# mcp2221-breakout.net
KiCad netlist of a schematic drawn in EAGLE
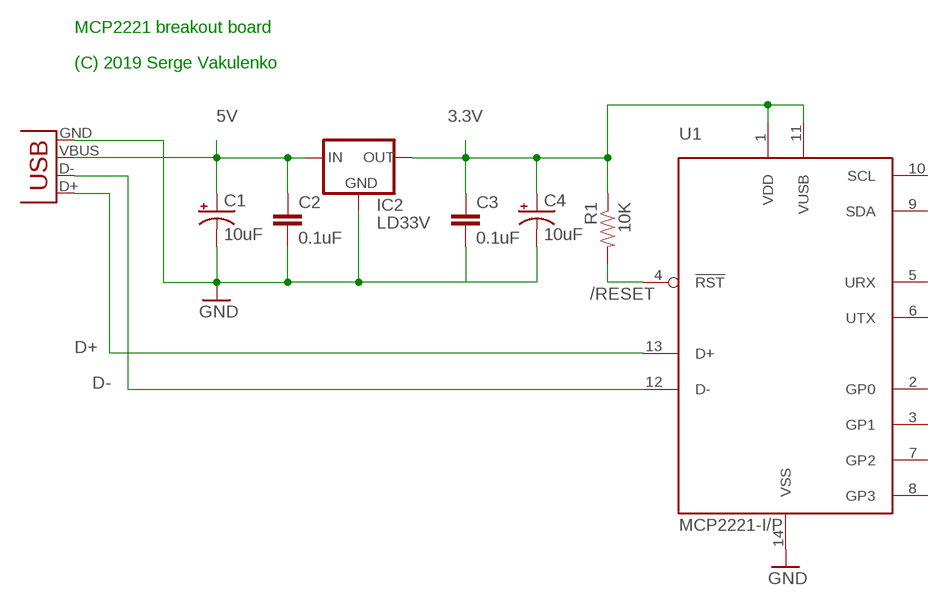
[diagram p0: schematic, sheet 1]

(export (version "E")
  (design (tool "Eeschema 10.0.6"))
  (components
    (comp (ref "C1")
      (value "10uF")
      (footprint "eagle-import:CPOL-RADIAL-10UF-25V")
      (libsource (lib "eagle-import") (part "CAP_POLPTH2"))
    )
    (comp (ref "C2")
      (value "0.1uF")
      (footprint "eagle-import:CAP-PTH-SMALL")
      (libsource (lib "eagle-import") (part "CAPPTH"))
    )
    (comp (ref "C3")
      (value "0.1uF")
      (footprint "eagle-import:CAP-PTH-5MM")
      (libsource (lib "eagle-import") (part "CAPPTH1"))
    )
    (comp (ref "C4")
      (value "10uF")
      (footprint "eagle-import:CPOL-RADIAL-10UF-25V")
      (libsource (lib "eagle-import") (part "CAP_POLPTH2"))
    )
    (comp (ref "IC2")
      (value "LD33V")
      (footprint "eagle-import:78XXL")
      (libsource (lib "eagle-import") (part "V_REG_78XXSIDE"))
    )
    (comp (ref "R1")
      (value "10K")
      (footprint "eagle-import:AXIAL-0.3")
      (libsource (lib "eagle-import") (part "RESISTORPTH1"))
    )
    (comp (ref "U1")
      (value "MCP2221-I/P")
      (footprint "eagle-import:DIL14")
      (libsource (lib "eagle-import") (part "MCP2221-I/P"))
    )
    (comp (ref "X1")
      (value "USBPTH")
      (footprint "eagle-import:USB-B-PTH")
      (libsource (lib "eagle-import") (part "USBPTH"))
    )
  )
  (nets
    (net (code "1") (name "/3.3V") (class "Default")
      (node (ref "C3") (pin "1") (pinfunction "1_1") (pintype "passive"))
      (node (ref "C4") (pin "1") (pinfunction "+_1") (pintype "passive"))
      (node (ref "IC2") (pin "OUT") (pinfunction "OUT_OUT") (pintype "output"))
      (node (ref "R1") (pin "P$1") (pinfunction "1_P$1") (pintype "passive"))
      (node (ref "U1") (pin "1") (pinfunction "VDD_1") (pintype "power_in"))
      (node (ref "U1") (pin "11") (pinfunction "VUSB_11") (pintype "power_in"))
    )
    (net (code "2") (name "/5V") (class "Default")
      (node (ref "C1") (pin "1") (pinfunction "+_1") (pintype "passive"))
      (node (ref "C2") (pin "1") (pinfunction "1_1") (pintype "passive"))
      (node (ref "IC2") (pin "IN") (pinfunction "IN_IN") (pintype "input"))
      (node (ref "X1") (pin "VBUS") (pinfunction "VBUS_VBUS") (pintype "bidirectional"))
    )
    (net (code "3") (name "/D+") (class "Default")
      (node (ref "U1") (pin "13") (pinfunction "D+_13") (pintype "bidirectional"))
      (node (ref "X1") (pin "D+") (pinfunction "D+_D+") (pintype "bidirectional"))
    )
    (net (code "4") (name "/D-") (class "Default")
      (node (ref "U1") (pin "12") (pinfunction "D-_12") (pintype "bidirectional"))
      (node (ref "X1") (pin "D-") (pinfunction "D-_D-") (pintype "bidirectional"))
    )
    (net (code "5") (name "/{slash}RESET") (class "Default")
      (node (ref "R1") (pin "P$2") (pinfunction "2_P$2") (pintype "passive"))
      (node (ref "U1") (pin "4") (pinfunction "~{RST}_4") (pintype "input"))
    )
    (net (code "6") (name "GND") (class "Default")
      (node (ref "C1") (pin "2") (pinfunction "-_2") (pintype "passive"))
      (node (ref "C2") (pin "2") (pinfunction "2_2") (pintype "passive"))
      (node (ref "C3") (pin "2") (pinfunction "2_2") (pintype "passive"))
      (node (ref "C4") (pin "2") (pinfunction "-_2") (pintype "passive"))
      (node (ref "IC2") (pin "GND") (pinfunction "GND_GND") (pintype "input"))
      (node (ref "U1") (pin "14") (pinfunction "VSS_14") (pintype "power_in"))
      (node (ref "X1") (pin "GND") (pinfunction "GND_GND") (pintype "bidirectional"))
    )
    (net (code "7") (name "unconnected-(U1-GP0-Pad2)") (class "Default")
      (node (ref "U1") (pin "2") (pinfunction "GP0_2") (pintype "bidirectional"))
    )
    (net (code "8") (name "unconnected-(U1-GP1-Pad3)") (class "Default")
      (node (ref "U1") (pin "3") (pinfunction "GP1_3") (pintype "bidirectional"))
    )
    (net (code "9") (name "unconnected-(U1-GP2-Pad7)") (class "Default")
      (node (ref "U1") (pin "7") (pinfunction "GP2_7") (pintype "bidirectional"))
    )
    (net (code "10") (name "unconnected-(U1-GP3-Pad8)") (class "Default")
      (node (ref "U1") (pin "8") (pinfunction "GP3_8") (pintype "bidirectional"))
    )
    (net (code "11") (name "unconnected-(U1-SCL-Pad10)") (class "Default")
      (node (ref "U1") (pin "10") (pinfunction "SCL_10") (pintype "output"))
    )
    (net (code "12") (name "unconnected-(U1-SDA-Pad9)") (class "Default")
      (node (ref "U1") (pin "9") (pinfunction "SDA_9") (pintype "bidirectional"))
    )
    (net (code "13") (name "unconnected-(U1-URX-Pad5)") (class "Default")
      (node (ref "U1") (pin "5") (pinfunction "URX_5") (pintype "input"))
    )
    (net (code "14") (name "unconnected-(U1-UTX-Pad6)") (class "Default")
      (node (ref "U1") (pin "6") (pinfunction "UTX_6") (pintype "output"))
    )
  )
)
